# HeadBoard.net
KiCad netlist of a schematic drawn in Altium Designer
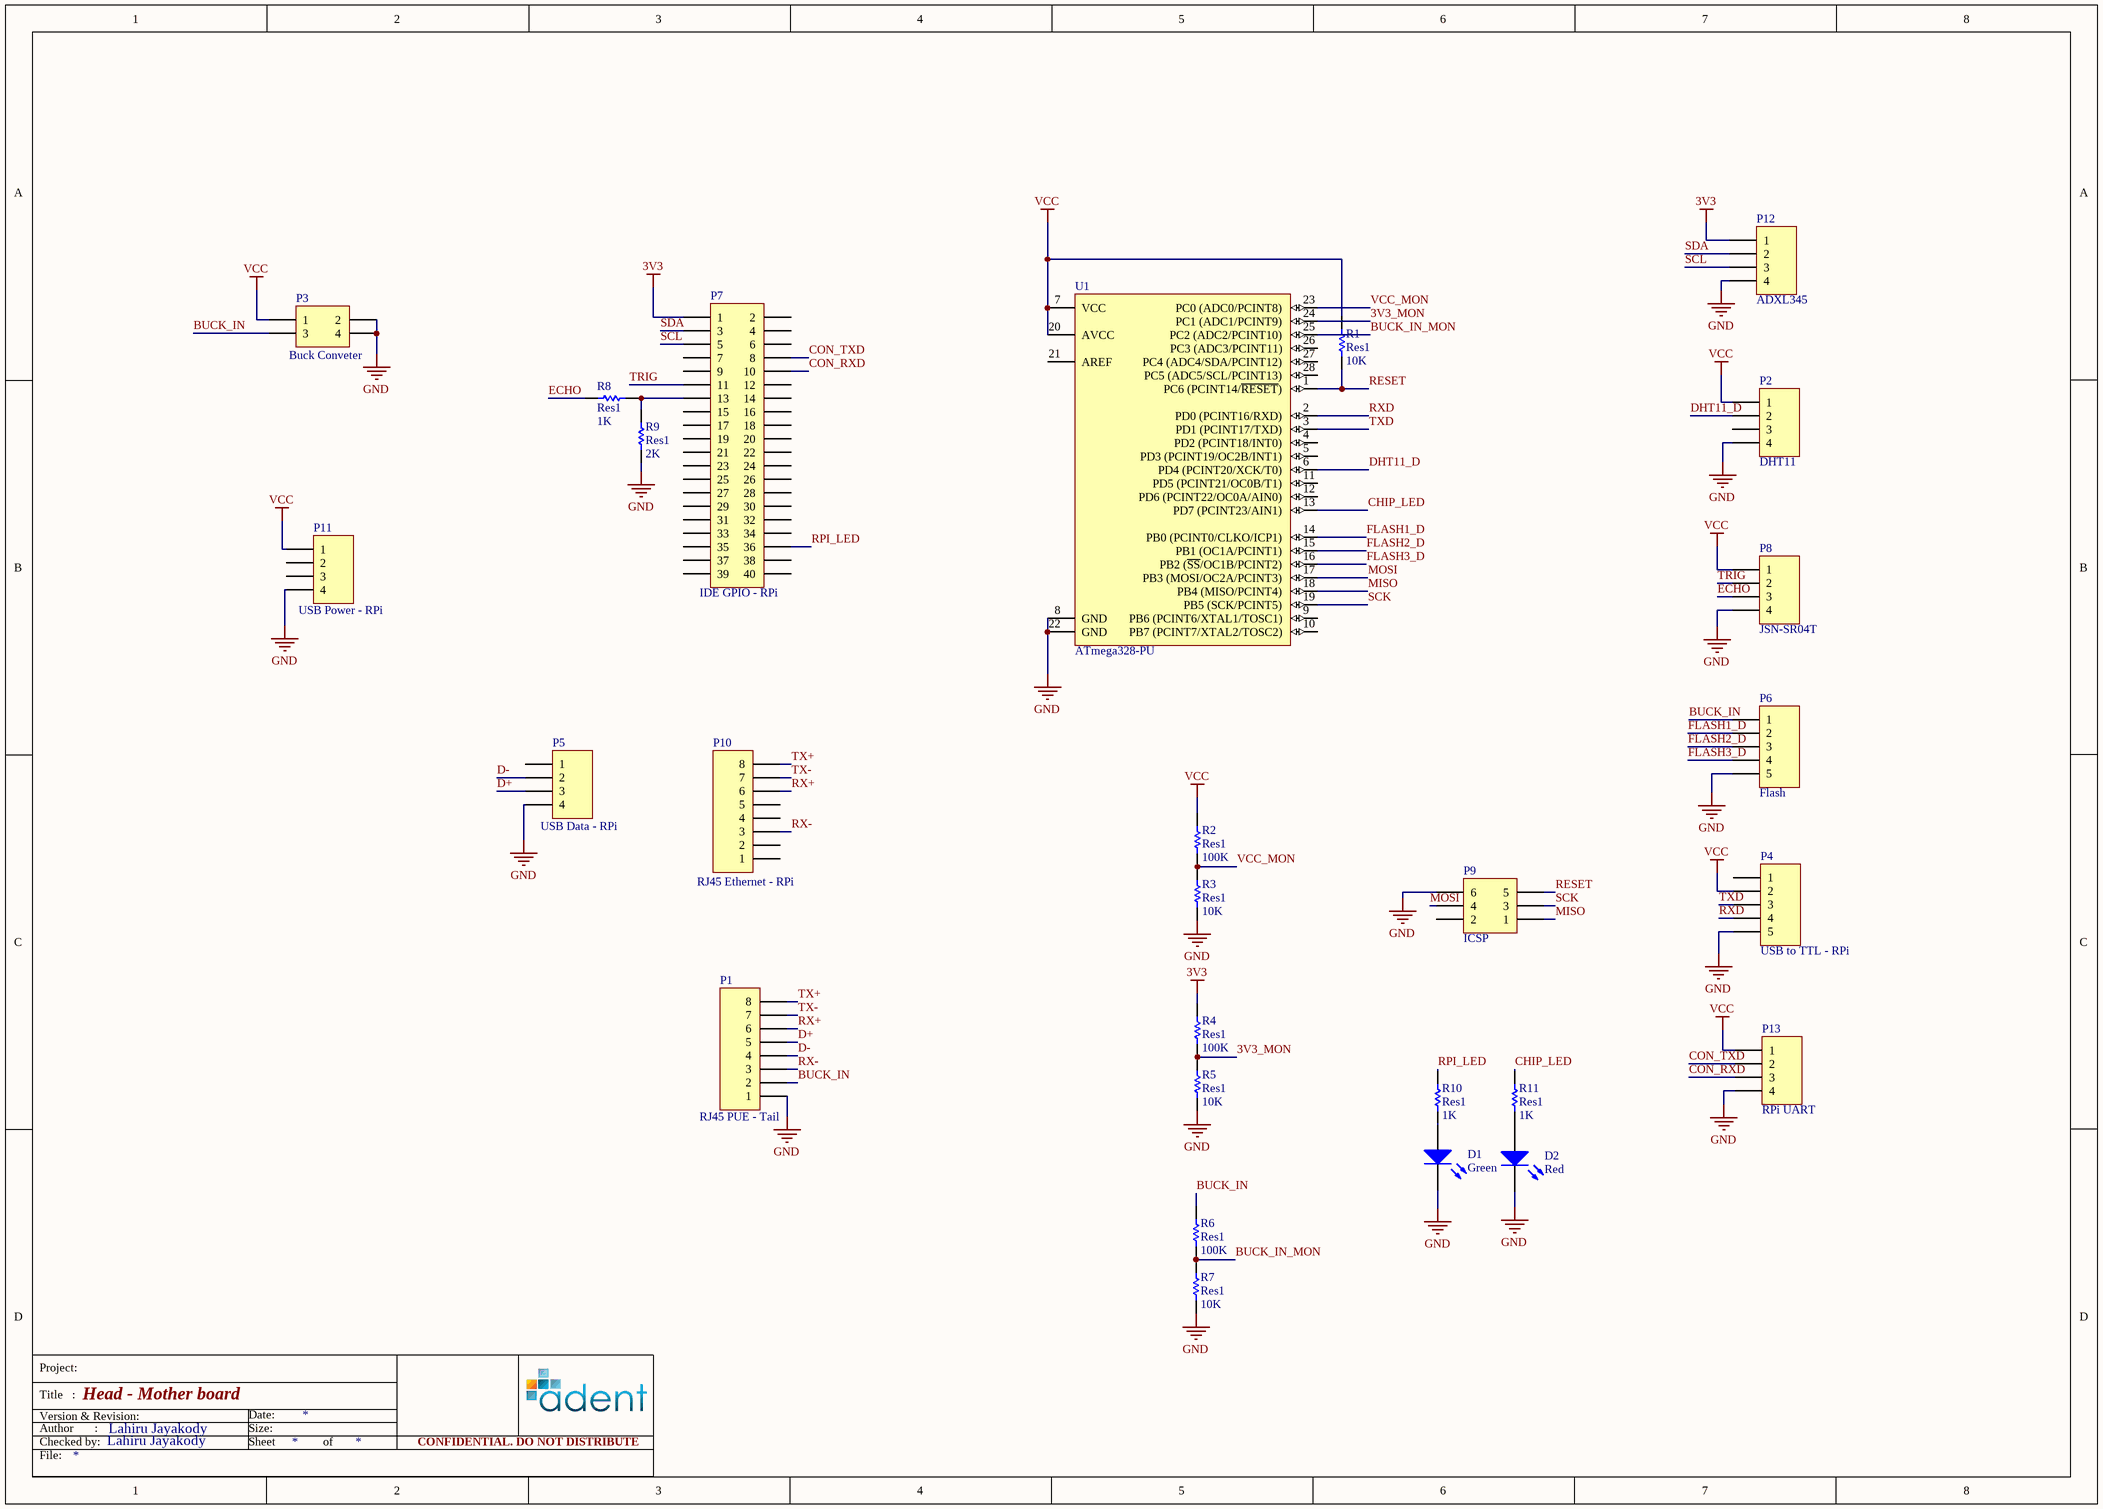
[diagram p0: HeadBoard.SchDoc]

(export (version "E")
  (design (tool "Eeschema 10.0.6"))
  (components
    (comp (ref "D1")
      (value "Green")
      (footprint "LED-1")
      (description "Typical RED GaAs LED")
      (fields (field (name "PUBLISHER") "Altium Limited"))
      (libsource (lib "Miscellaneous Devices") (part "LED1"))
    )
    (comp (ref "D2")
      (value "Red")
      (footprint "LED-1")
      (description "Typical RED GaAs LED")
      (fields (field (name "PUBLISHER") "Altium Limited"))
      (libsource (lib "Miscellaneous Devices") (part "LED1"))
    )
    (comp (ref "P1")
      (value "RJ45 PUE - Tail")
      (footprint "RJ45")
      (description "Header, 8-Pin")
      (fields (field (name "PUBLISHER") "Altium Limited"))
      (libsource (lib "Miscellaneous Connectors") (part "Header 8"))
    )
    (comp (ref "P2")
      (value "DHT11")
      (footprint "HDR1X4")
      (description "Header, 4-Pin")
      (fields (field (name "PUBLISHER") "Altium Limited"))
      (libsource (lib "Miscellaneous Connectors") (part "Header 4"))
    )
    (comp (ref "P3")
      (value "Buck Conveter")
      (footprint "HDR2X2")
      (description "Header, 2-Pin, Dual row")
      (fields (field (name "PUBLISHER") "Altium Limited"))
      (libsource (lib "Miscellaneous Connectors") (part "Header 2X2"))
    )
    (comp (ref "P4")
      (value "USB to TTL - RPi")
      (footprint "HDR1X5")
      (description "Header, 5-Pin")
      (fields (field (name "PUBLISHER") "Altium Limited"))
      (libsource (lib "Miscellaneous Connectors") (part "Header 5"))
    )
    (comp (ref "P5")
      (value "USB Data - RPi")
      (footprint "USB_Female")
      (description "Header, 4-Pin")
      (fields (field (name "PUBLISHER") "Altium Limited"))
      (libsource (lib "Miscellaneous Connectors") (part "Header 4"))
    )
    (comp (ref "P6")
      (value "Flash")
      (footprint "HDR1X5")
      (description "Header, 5-Pin")
      (fields (field (name "PUBLISHER") "Altium Limited"))
      (libsource (lib "Miscellaneous Connectors") (part "Header 5"))
    )
    (comp (ref "P7")
      (value "IDE GPIO - RPi")
      (footprint "HDR2X20")
      (description "Header, 20-Pin, Dual row")
      (fields (field (name "PUBLISHER") "Altium Limited"))
      (libsource (lib "Miscellaneous Connectors") (part "Header 20X2"))
    )
    (comp (ref "P8")
      (value "JSN-SR04T")
      (footprint "HDR1X4")
      (description "Header, 4-Pin")
      (fields (field (name "PUBLISHER") "Altium Limited"))
      (libsource (lib "Miscellaneous Connectors") (part "Header 4"))
    )
    (comp (ref "P9")
      (value "ICSP")
      (footprint "HDR2X3")
      (description "Header, 3-Pin, Dual row")
      (fields (field (name "PUBLISHER") "Altium Limited"))
      (libsource (lib "Miscellaneous Connectors") (part "Header 3X2"))
    )
    (comp (ref "P10")
      (value "RJ45 Ethernet - RPi")
      (footprint "RJ45")
      (description "Header, 8-Pin")
      (fields (field (name "PUBLISHER") "Altium Limited"))
      (libsource (lib "Miscellaneous Connectors") (part "Header 8"))
    )
    (comp (ref "P11")
      (value "USB Power - RPi")
      (footprint "USB_Female")
      (description "Header, 4-Pin")
      (fields (field (name "PUBLISHER") "Altium Limited"))
      (libsource (lib "Miscellaneous Connectors") (part "Header 4"))
    )
    (comp (ref "P12")
      (value "ADXL345")
      (footprint "HDR1X4")
      (description "Header, 4-Pin")
      (fields (field (name "PUBLISHER") "Altium Limited"))
      (libsource (lib "Miscellaneous Connectors") (part "Header 4"))
    )
    (comp (ref "P13")
      (value "RPi UART")
      (footprint "HDR1X4")
      (description "Header, 4-Pin")
      (fields (field (name "PUBLISHER") "Altium Limited"))
      (libsource (lib "Miscellaneous Connectors") (part "Header 4"))
    )
    (comp (ref "R1")
      (value "Res1")
      (footprint "AXIAL-0.3")
      (description "Resistor")
      (fields (field (name "ALTIUM_VALUE") "10K") (field (name "PUBLISHER") "Altium Limited"))
      (libsource (lib "Miscellaneous Devices") (part "Res1"))
    )
    (comp (ref "R2")
      (value "Res1")
      (footprint "AXIAL-0.3")
      (description "Resistor")
      (fields (field (name "ALTIUM_VALUE") "100K") (field (name "PUBLISHER") "Altium Limited"))
      (libsource (lib "Miscellaneous Devices") (part "Res1"))
    )
    (comp (ref "R3")
      (value "Res1")
      (footprint "AXIAL-0.3")
      (description "Resistor")
      (fields (field (name "ALTIUM_VALUE") "10K") (field (name "PUBLISHER") "Altium Limited"))
      (libsource (lib "Miscellaneous Devices") (part "Res1"))
    )
    (comp (ref "R4")
      (value "Res1")
      (footprint "AXIAL-0.3")
      (description "Resistor")
      (fields (field (name "ALTIUM_VALUE") "100K") (field (name "PUBLISHER") "Altium Limited"))
      (libsource (lib "Miscellaneous Devices") (part "Res1"))
    )
    (comp (ref "R5")
      (value "Res1")
      (footprint "AXIAL-0.3")
      (description "Resistor")
      (fields (field (name "ALTIUM_VALUE") "10K") (field (name "PUBLISHER") "Altium Limited"))
      (libsource (lib "Miscellaneous Devices") (part "Res1"))
    )
    (comp (ref "R6")
      (value "Res1")
      (footprint "AXIAL-0.3")
      (description "Resistor")
      (fields (field (name "ALTIUM_VALUE") "100K") (field (name "PUBLISHER") "Altium Limited"))
      (libsource (lib "Miscellaneous Devices") (part "Res1"))
    )
    (comp (ref "R7")
      (value "Res1")
      (footprint "AXIAL-0.3")
      (description "Resistor")
      (fields (field (name "ALTIUM_VALUE") "10K") (field (name "PUBLISHER") "Altium Limited"))
      (libsource (lib "Miscellaneous Devices") (part "Res1"))
    )
    (comp (ref "R8")
      (value "Res1")
      (footprint "AXIAL-0.3")
      (description "Resistor")
      (fields (field (name "ALTIUM_VALUE") "1K") (field (name "PUBLISHER") "Altium Limited"))
      (libsource (lib "Miscellaneous Devices") (part "Res1"))
    )
    (comp (ref "R9")
      (value "Res1")
      (footprint "AXIAL-0.3")
      (description "Resistor")
      (fields (field (name "ALTIUM_VALUE") "2K") (field (name "PUBLISHER") "Altium Limited"))
      (libsource (lib "Miscellaneous Devices") (part "Res1"))
    )
    (comp (ref "R10")
      (value "Res1")
      (footprint "AXIAL-0.3")
      (description "Resistor")
      (fields (field (name "ALTIUM_VALUE") "1K") (field (name "PUBLISHER") "Altium Limited"))
      (libsource (lib "Miscellaneous Devices") (part "Res1"))
    )
    (comp (ref "R11")
      (value "Res1")
      (footprint "AXIAL-0.3")
      (description "Resistor")
      (fields (field (name "ALTIUM_VALUE") "1K") (field (name "PUBLISHER") "Altium Limited"))
      (libsource (lib "Miscellaneous Devices") (part "Res1"))
    )
    (comp (ref "U1")
      (value "ATmega328-PU")
      (footprint "28P3")
      (fields (field (name "PUBLISHER") "Altium Limited"))
      (libsource (lib "Atmel Microcontroller 8-Bit megaAVR") (part "ATmega328-PU"))
    )
  )
  (nets
    (net (code "1") (name "/3V3_MON") (class "Default")
      (node (ref "R4") (pin "1") (pinfunction "1_1") (pintype "passive"))
      (node (ref "R5") (pin "2") (pinfunction "2_2") (pintype "passive"))
      (node (ref "U1") (pin "24") (pinfunction "PC1_(ADC1/PCINT9)_24") (pintype "bidirectional"))
    )
    (net (code "2") (name "/BUCK_IN") (class "Default")
      (node (ref "P1") (pin "2") (pinfunction "2_2") (pintype "passive"))
      (node (ref "P3") (pin "3") (pinfunction "3_3") (pintype "passive"))
      (node (ref "P6") (pin "1") (pinfunction "1_1") (pintype "passive"))
      (node (ref "R6") (pin "2") (pinfunction "2_2") (pintype "passive"))
    )
    (net (code "3") (name "/BUCK_IN_MON") (class "Default")
      (node (ref "R6") (pin "1") (pinfunction "1_1") (pintype "passive"))
      (node (ref "R7") (pin "2") (pinfunction "2_2") (pintype "passive"))
      (node (ref "U1") (pin "25") (pinfunction "PC2_(ADC2/PCINT10)_25") (pintype "bidirectional"))
    )
    (net (code "4") (name "/CHIP_LED") (class "Default")
      (node (ref "R11") (pin "2") (pinfunction "2_2") (pintype "passive"))
      (node (ref "U1") (pin "13") (pinfunction "PD7_(PCINT23/AIN1)_13") (pintype "bidirectional"))
    )
    (net (code "5") (name "/CON_RXD") (class "Default")
      (node (ref "P13") (pin "3") (pinfunction "3_3") (pintype "passive"))
      (node (ref "P7") (pin "10") (pinfunction "10_10") (pintype "passive"))
    )
    (net (code "6") (name "/CON_TXD") (class "Default")
      (node (ref "P13") (pin "2") (pinfunction "2_2") (pintype "passive"))
      (node (ref "P7") (pin "8") (pinfunction "8_8") (pintype "passive"))
    )
    (net (code "7") (name "/D+") (class "Default")
      (node (ref "P1") (pin "5") (pinfunction "5_5") (pintype "passive"))
      (node (ref "P5") (pin "3") (pinfunction "3_3") (pintype "passive"))
    )
    (net (code "8") (name "/D-") (class "Default")
      (node (ref "P1") (pin "4") (pinfunction "4_4") (pintype "passive"))
      (node (ref "P5") (pin "2") (pinfunction "2_2") (pintype "passive"))
    )
    (net (code "9") (name "/DHT11_D") (class "Default")
      (node (ref "P2") (pin "2") (pinfunction "2_2") (pintype "passive"))
      (node (ref "U1") (pin "6") (pinfunction "PD4_(PCINT20/XCK/T0)_6") (pintype "bidirectional"))
    )
    (net (code "10") (name "/ECHO") (class "Default")
      (node (ref "P8") (pin "3") (pinfunction "3_3") (pintype "passive"))
      (node (ref "R8") (pin "1") (pinfunction "1_1") (pintype "passive"))
    )
    (net (code "11") (name "/FLASH1_D") (class "Default")
      (node (ref "P6") (pin "2") (pinfunction "2_2") (pintype "passive"))
      (node (ref "U1") (pin "14") (pinfunction "PB0_(PCINT0/CLKO/ICP1)_14") (pintype "bidirectional"))
    )
    (net (code "12") (name "/FLASH2_D") (class "Default")
      (node (ref "P6") (pin "3") (pinfunction "3_3") (pintype "passive"))
      (node (ref "U1") (pin "15") (pinfunction "PB1_(OC1A/PCINT1)_15") (pintype "bidirectional"))
    )
    (net (code "13") (name "/FLASH3_D") (class "Default")
      (node (ref "P6") (pin "4") (pinfunction "4_4") (pintype "passive"))
      (node (ref "U1") (pin "16") (pinfunction "PB2_(~{SS}/OC1B/PCINT2)_16") (pintype "bidirectional"))
    )
    (net (code "14") (name "/MISO") (class "Default")
      (node (ref "P9") (pin "1") (pinfunction "1_1") (pintype "passive"))
      (node (ref "U1") (pin "18") (pinfunction "PB4_(MISO/PCINT4)_18") (pintype "bidirectional"))
    )
    (net (code "15") (name "/MOSI") (class "Default")
      (node (ref "P9") (pin "4") (pinfunction "4_4") (pintype "passive"))
      (node (ref "U1") (pin "17") (pinfunction "PB3_(MOSI/OC2A/PCINT3)_17") (pintype "bidirectional"))
    )
    (net (code "16") (name "/RESET") (class "Default")
      (node (ref "P9") (pin "5") (pinfunction "5_5") (pintype "passive"))
      (node (ref "R1") (pin "1") (pinfunction "1_1") (pintype "passive"))
      (node (ref "U1") (pin "1") (pinfunction "PC6_(PCINT14/~{RESET})_1") (pintype "bidirectional"))
    )
    (net (code "17") (name "/RPI_LED") (class "Default")
      (node (ref "P7") (pin "36") (pinfunction "36_36") (pintype "passive"))
      (node (ref "R10") (pin "2") (pinfunction "2_2") (pintype "passive"))
    )
    (net (code "18") (name "/RX+") (class "Default")
      (node (ref "P1") (pin "6") (pinfunction "6_6") (pintype "passive"))
      (node (ref "P10") (pin "6") (pinfunction "6_6") (pintype "passive"))
    )
    (net (code "19") (name "/RX-") (class "Default")
      (node (ref "P1") (pin "3") (pinfunction "3_3") (pintype "passive"))
      (node (ref "P10") (pin "3") (pinfunction "3_3") (pintype "passive"))
    )
    (net (code "20") (name "/RXD") (class "Default")
      (node (ref "P4") (pin "4") (pinfunction "4_4") (pintype "passive"))
      (node (ref "U1") (pin "2") (pinfunction "PD0_(PCINT16/RXD)_2") (pintype "bidirectional"))
    )
    (net (code "21") (name "/SCK") (class "Default")
      (node (ref "P9") (pin "3") (pinfunction "3_3") (pintype "passive"))
      (node (ref "U1") (pin "19") (pinfunction "PB5_(SCK/PCINT5)_19") (pintype "bidirectional"))
    )
    (net (code "22") (name "/SCL") (class "Default")
      (node (ref "P12") (pin "3") (pinfunction "3_3") (pintype "passive"))
      (node (ref "P7") (pin "5") (pinfunction "5_5") (pintype "passive"))
    )
    (net (code "23") (name "/SDA") (class "Default")
      (node (ref "P12") (pin "2") (pinfunction "2_2") (pintype "passive"))
      (node (ref "P7") (pin "3") (pinfunction "3_3") (pintype "passive"))
    )
    (net (code "24") (name "/TRIG") (class "Default")
      (node (ref "P7") (pin "11") (pinfunction "11_11") (pintype "passive"))
      (node (ref "P8") (pin "2") (pinfunction "2_2") (pintype "passive"))
    )
    (net (code "25") (name "/TX+") (class "Default")
      (node (ref "P1") (pin "8") (pinfunction "8_8") (pintype "passive"))
      (node (ref "P10") (pin "8") (pinfunction "8_8") (pintype "passive"))
    )
    (net (code "26") (name "/TX-") (class "Default")
      (node (ref "P1") (pin "7") (pinfunction "7_7") (pintype "passive"))
      (node (ref "P10") (pin "7") (pinfunction "7_7") (pintype "passive"))
    )
    (net (code "27") (name "/TXD") (class "Default")
      (node (ref "P4") (pin "3") (pinfunction "3_3") (pintype "passive"))
      (node (ref "U1") (pin "3") (pinfunction "PD1_(PCINT17/TXD)_3") (pintype "bidirectional"))
    )
    (net (code "28") (name "/VCC_MON") (class "Default")
      (node (ref "R2") (pin "1") (pinfunction "1_1") (pintype "passive"))
      (node (ref "R3") (pin "2") (pinfunction "2_2") (pintype "passive"))
      (node (ref "U1") (pin "23") (pinfunction "PC0_(ADC0/PCINT8)_23") (pintype "bidirectional"))
    )
    (net (code "29") (name "3V3") (class "Default")
      (node (ref "P12") (pin "1") (pinfunction "1_1") (pintype "passive"))
      (node (ref "P7") (pin "1") (pinfunction "1_1") (pintype "passive"))
      (node (ref "R4") (pin "2") (pinfunction "2_2") (pintype "passive"))
    )
    (net (code "30") (name "GND") (class "Default")
      (node (ref "D1") (pin "2") (pinfunction "K_2") (pintype "passive"))
      (node (ref "D2") (pin "2") (pinfunction "K_2") (pintype "passive"))
      (node (ref "P1") (pin "1") (pinfunction "1_1") (pintype "passive"))
      (node (ref "P11") (pin "4") (pinfunction "4_4") (pintype "passive"))
      (node (ref "P12") (pin "4") (pinfunction "4_4") (pintype "passive"))
      (node (ref "P13") (pin "4") (pinfunction "4_4") (pintype "passive"))
      (node (ref "P2") (pin "4") (pinfunction "4_4") (pintype "passive"))
      (node (ref "P3") (pin "2") (pinfunction "2_2") (pintype "passive"))
      (node (ref "P3") (pin "4") (pinfunction "4_4") (pintype "passive"))
      (node (ref "P4") (pin "5") (pinfunction "5_5") (pintype "passive"))
      (node (ref "P5") (pin "4") (pinfunction "4_4") (pintype "passive"))
      (node (ref "P6") (pin "5") (pinfunction "5_5") (pintype "passive"))
      (node (ref "P8") (pin "4") (pinfunction "4_4") (pintype "passive"))
      (node (ref "P9") (pin "6") (pinfunction "6_6") (pintype "passive"))
      (node (ref "R3") (pin "1") (pinfunction "1_1") (pintype "passive"))
      (node (ref "R5") (pin "1") (pinfunction "1_1") (pintype "passive"))
      (node (ref "R7") (pin "1") (pinfunction "1_1") (pintype "passive"))
      (node (ref "R9") (pin "1") (pinfunction "1_1") (pintype "passive"))
      (node (ref "U1") (pin "22") (pinfunction "GND_22") (pintype "power_in"))
      (node (ref "U1") (pin "8") (pinfunction "GND_8") (pintype "power_in"))
    )
    (net (code "31") (name "Net-(D1-A)") (class "Default")
      (node (ref "D1") (pin "1") (pinfunction "A_1") (pintype "passive"))
      (node (ref "R10") (pin "1") (pinfunction "1_1") (pintype "passive"))
    )
    (net (code "32") (name "Net-(D2-A)") (class "Default")
      (node (ref "D2") (pin "1") (pinfunction "A_1") (pintype "passive"))
      (node (ref "R11") (pin "1") (pinfunction "1_1") (pintype "passive"))
    )
    (net (code "33") (name "Net-(P7-Pad13)") (class "Default")
      (node (ref "P7") (pin "13") (pinfunction "13_13") (pintype "passive"))
      (node (ref "R8") (pin "2") (pinfunction "2_2") (pintype "passive"))
      (node (ref "R9") (pin "2") (pinfunction "2_2") (pintype "passive"))
    )
    (net (code "34") (name "VCC") (class "Default")
      (node (ref "P11") (pin "1") (pinfunction "1_1") (pintype "passive"))
      (node (ref "P13") (pin "1") (pinfunction "1_1") (pintype "passive"))
      (node (ref "P2") (pin "1") (pinfunction "1_1") (pintype "passive"))
      (node (ref "P3") (pin "1") (pinfunction "1_1") (pintype "passive"))
      (node (ref "P4") (pin "2") (pinfunction "2_2") (pintype "passive"))
      (node (ref "P8") (pin "1") (pinfunction "1_1") (pintype "passive"))
      (node (ref "R1") (pin "2") (pinfunction "2_2") (pintype "passive"))
      (node (ref "R2") (pin "2") (pinfunction "2_2") (pintype "passive"))
      (node (ref "U1") (pin "20") (pinfunction "AVCC_20") (pintype "power_in"))
      (node (ref "U1") (pin "7") (pinfunction "VCC_7") (pintype "power_in"))
    )
    (net (code "35") (name "unconnected-(P2-Pad3)") (class "Default")
      (node (ref "P2") (pin "3") (pinfunction "3_3") (pintype "passive"))
    )
    (net (code "36") (name "unconnected-(P4-Pad1)") (class "Default")
      (node (ref "P4") (pin "1") (pinfunction "1_1") (pintype "passive"))
    )
    (net (code "37") (name "unconnected-(P5-Pad1)") (class "Default")
      (node (ref "P5") (pin "1") (pinfunction "1_1") (pintype "passive"))
    )
    (net (code "38") (name "unconnected-(P7-Pad2)") (class "Default")
      (node (ref "P7") (pin "2") (pinfunction "2_2") (pintype "passive"))
    )
    (net (code "39") (name "unconnected-(P7-Pad4)") (class "Default")
      (node (ref "P7") (pin "4") (pinfunction "4_4") (pintype "passive"))
    )
    (net (code "40") (name "unconnected-(P7-Pad6)") (class "Default")
      (node (ref "P7") (pin "6") (pinfunction "6_6") (pintype "passive"))
    )
    (net (code "41") (name "unconnected-(P7-Pad7)") (class "Default")
      (node (ref "P7") (pin "7") (pinfunction "7_7") (pintype "passive"))
    )
    (net (code "42") (name "unconnected-(P7-Pad9)") (class "Default")
      (node (ref "P7") (pin "9") (pinfunction "9_9") (pintype "passive"))
    )
    (net (code "43") (name "unconnected-(P7-Pad12)") (class "Default")
      (node (ref "P7") (pin "12") (pinfunction "12_12") (pintype "passive"))
    )
    (net (code "44") (name "unconnected-(P7-Pad14)") (class "Default")
      (node (ref "P7") (pin "14") (pinfunction "14_14") (pintype "passive"))
    )
    (net (code "45") (name "unconnected-(P7-Pad15)") (class "Default")
      (node (ref "P7") (pin "15") (pinfunction "15_15") (pintype "passive"))
    )
    (net (code "46") (name "unconnected-(P7-Pad16)") (class "Default")
      (node (ref "P7") (pin "16") (pinfunction "16_16") (pintype "passive"))
    )
    (net (code "47") (name "unconnected-(P7-Pad17)") (class "Default")
      (node (ref "P7") (pin "17") (pinfunction "17_17") (pintype "passive"))
    )
    (net (code "48") (name "unconnected-(P7-Pad18)") (class "Default")
      (node (ref "P7") (pin "18") (pinfunction "18_18") (pintype "passive"))
    )
    (net (code "49") (name "unconnected-(P7-Pad19)") (class "Default")
      (node (ref "P7") (pin "19") (pinfunction "19_19") (pintype "passive"))
    )
    (net (code "50") (name "unconnected-(P7-Pad20)") (class "Default")
      (node (ref "P7") (pin "20") (pinfunction "20_20") (pintype "passive"))
    )
    (net (code "51") (name "unconnected-(P7-Pad21)") (class "Default")
      (node (ref "P7") (pin "21") (pinfunction "21_21") (pintype "passive"))
    )
    (net (code "52") (name "unconnected-(P7-Pad22)") (class "Default")
      (node (ref "P7") (pin "22") (pinfunction "22_22") (pintype "passive"))
    )
    (net (code "53") (name "unconnected-(P7-Pad23)") (class "Default")
      (node (ref "P7") (pin "23") (pinfunction "23_23") (pintype "passive"))
    )
    (net (code "54") (name "unconnected-(P7-Pad24)") (class "Default")
      (node (ref "P7") (pin "24") (pinfunction "24_24") (pintype "passive"))
    )
    (net (code "55") (name "unconnected-(P7-Pad25)") (class "Default")
      (node (ref "P7") (pin "25") (pinfunction "25_25") (pintype "passive"))
    )
    (net (code "56") (name "unconnected-(P7-Pad26)") (class "Default")
      (node (ref "P7") (pin "26") (pinfunction "26_26") (pintype "passive"))
    )
    (net (code "57") (name "unconnected-(P7-Pad27)") (class "Default")
      (node (ref "P7") (pin "27") (pinfunction "27_27") (pintype "passive"))
    )
    (net (code "58") (name "unconnected-(P7-Pad28)") (class "Default")
      (node (ref "P7") (pin "28") (pinfunction "28_28") (pintype "passive"))
    )
    (net (code "59") (name "unconnected-(P7-Pad29)") (class "Default")
      (node (ref "P7") (pin "29") (pinfunction "29_29") (pintype "passive"))
    )
    (net (code "60") (name "unconnected-(P7-Pad30)") (class "Default")
      (node (ref "P7") (pin "30") (pinfunction "30_30") (pintype "passive"))
    )
    (net (code "61") (name "unconnected-(P7-Pad31)") (class "Default")
      (node (ref "P7") (pin "31") (pinfunction "31_31") (pintype "passive"))
    )
    (net (code "62") (name "unconnected-(P7-Pad32)") (class "Default")
      (node (ref "P7") (pin "32") (pinfunction "32_32") (pintype "passive"))
    )
    (net (code "63") (name "unconnected-(P7-Pad33)") (class "Default")
      (node (ref "P7") (pin "33") (pinfunction "33_33") (pintype "passive"))
    )
    (net (code "64") (name "unconnected-(P7-Pad34)") (class "Default")
      (node (ref "P7") (pin "34") (pinfunction "34_34") (pintype "passive"))
    )
    (net (code "65") (name "unconnected-(P7-Pad35)") (class "Default")
      (node (ref "P7") (pin "35") (pinfunction "35_35") (pintype "passive"))
    )
    (net (code "66") (name "unconnected-(P7-Pad37)") (class "Default")
      (node (ref "P7") (pin "37") (pinfunction "37_37") (pintype "passive"))
    )
    (net (code "67") (name "unconnected-(P7-Pad38)") (class "Default")
      (node (ref "P7") (pin "38") (pinfunction "38_38") (pintype "passive"))
    )
    (net (code "68") (name "unconnected-(P7-Pad39)") (class "Default")
      (node (ref "P7") (pin "39") (pinfunction "39_39") (pintype "passive"))
    )
    (net (code "69") (name "unconnected-(P7-Pad40)") (class "Default")
      (node (ref "P7") (pin "40") (pinfunction "40_40") (pintype "passive"))
    )
    (net (code "70") (name "unconnected-(P9-Pad2)") (class "Default")
      (node (ref "P9") (pin "2") (pinfunction "2_2") (pintype "passive"))
    )
    (net (code "71") (name "unconnected-(P10-Pad1)") (class "Default")
      (node (ref "P10") (pin "1") (pinfunction "1_1") (pintype "passive"))
    )
    (net (code "72") (name "unconnected-(P10-Pad2)") (class "Default")
      (node (ref "P10") (pin "2") (pinfunction "2_2") (pintype "passive"))
    )
    (net (code "73") (name "unconnected-(P10-Pad4)") (class "Default")
      (node (ref "P10") (pin "4") (pinfunction "4_4") (pintype "passive"))
    )
    (net (code "74") (name "unconnected-(P10-Pad5)") (class "Default")
      (node (ref "P10") (pin "5") (pinfunction "5_5") (pintype "passive"))
    )
    (net (code "75") (name "unconnected-(P11-Pad2)") (class "Default")
      (node (ref "P11") (pin "2") (pinfunction "2_2") (pintype "passive"))
    )
    (net (code "76") (name "unconnected-(P11-Pad3)") (class "Default")
      (node (ref "P11") (pin "3") (pinfunction "3_3") (pintype "passive"))
    )
    (net (code "77") (name "unconnected-(U1-AREF-Pad21)") (class "Default")
      (node (ref "U1") (pin "21") (pinfunction "AREF_21") (pintype "power_in"))
    )
    (net (code "78") (name "unconnected-(U1-PB6_(PCINT6{slash}XTAL1{slash}TOSC1)-Pad9)") (class "Default")
      (node (ref "U1") (pin "9") (pinfunction "PB6_(PCINT6/XTAL1/TOSC1)_9") (pintype "bidirectional"))
    )
    (net (code "79") (name "unconnected-(U1-PB7_(PCINT7{slash}XTAL2{slash}TOSC2)-Pad10)") (class "Default")
      (node (ref "U1") (pin "10") (pinfunction "PB7_(PCINT7/XTAL2/TOSC2)_10") (pintype "bidirectional"))
    )
    (net (code "80") (name "unconnected-(U1-PC3_(ADC3{slash}PCINT11)-Pad26)") (class "Default")
      (node (ref "U1") (pin "26") (pinfunction "PC3_(ADC3/PCINT11)_26") (pintype "bidirectional"))
    )
    (net (code "81") (name "unconnected-(U1-PC4_(ADC4{slash}SDA{slash}PCINT12)-Pad27)") (class "Default")
      (node (ref "U1") (pin "27") (pinfunction "PC4_(ADC4/SDA/PCINT12)_27") (pintype "bidirectional"))
    )
    (net (code "82") (name "unconnected-(U1-PC5_(ADC5{slash}SCL{slash}PCINT13)-Pad28)") (class "Default")
      (node (ref "U1") (pin "28") (pinfunction "PC5_(ADC5/SCL/PCINT13)_28") (pintype "bidirectional"))
    )
    (net (code "83") (name "unconnected-(U1-PD2_(PCINT18{slash}INT0)-Pad4)") (class "Default")
      (node (ref "U1") (pin "4") (pinfunction "PD2_(PCINT18/INT0)_4") (pintype "bidirectional"))
    )
    (net (code "84") (name "unconnected-(U1-PD3_(PCINT19{slash}OC2B{slash}INT1)-Pad5)") (class "Default")
      (node (ref "U1") (pin "5") (pinfunction "PD3_(PCINT19/OC2B/INT1)_5") (pintype "bidirectional"))
    )
    (net (code "85") (name "unconnected-(U1-PD5_(PCINT21{slash}OC0B{slash}T1)-Pad11)") (class "Default")
      (node (ref "U1") (pin "11") (pinfunction "PD5_(PCINT21/OC0B/T1)_11") (pintype "bidirectional"))
    )
    (net (code "86") (name "unconnected-(U1-PD6_(PCINT22{slash}OC0A{slash}AIN0)-Pad12)") (class "Default")
      (node (ref "U1") (pin "12") (pinfunction "PD6_(PCINT22/OC0A/AIN0)_12") (pintype "bidirectional"))
    )
  )
)
